# Binary_Sequencer_board2_controls.net
KiCad netlist of a schematic drawn in EAGLE
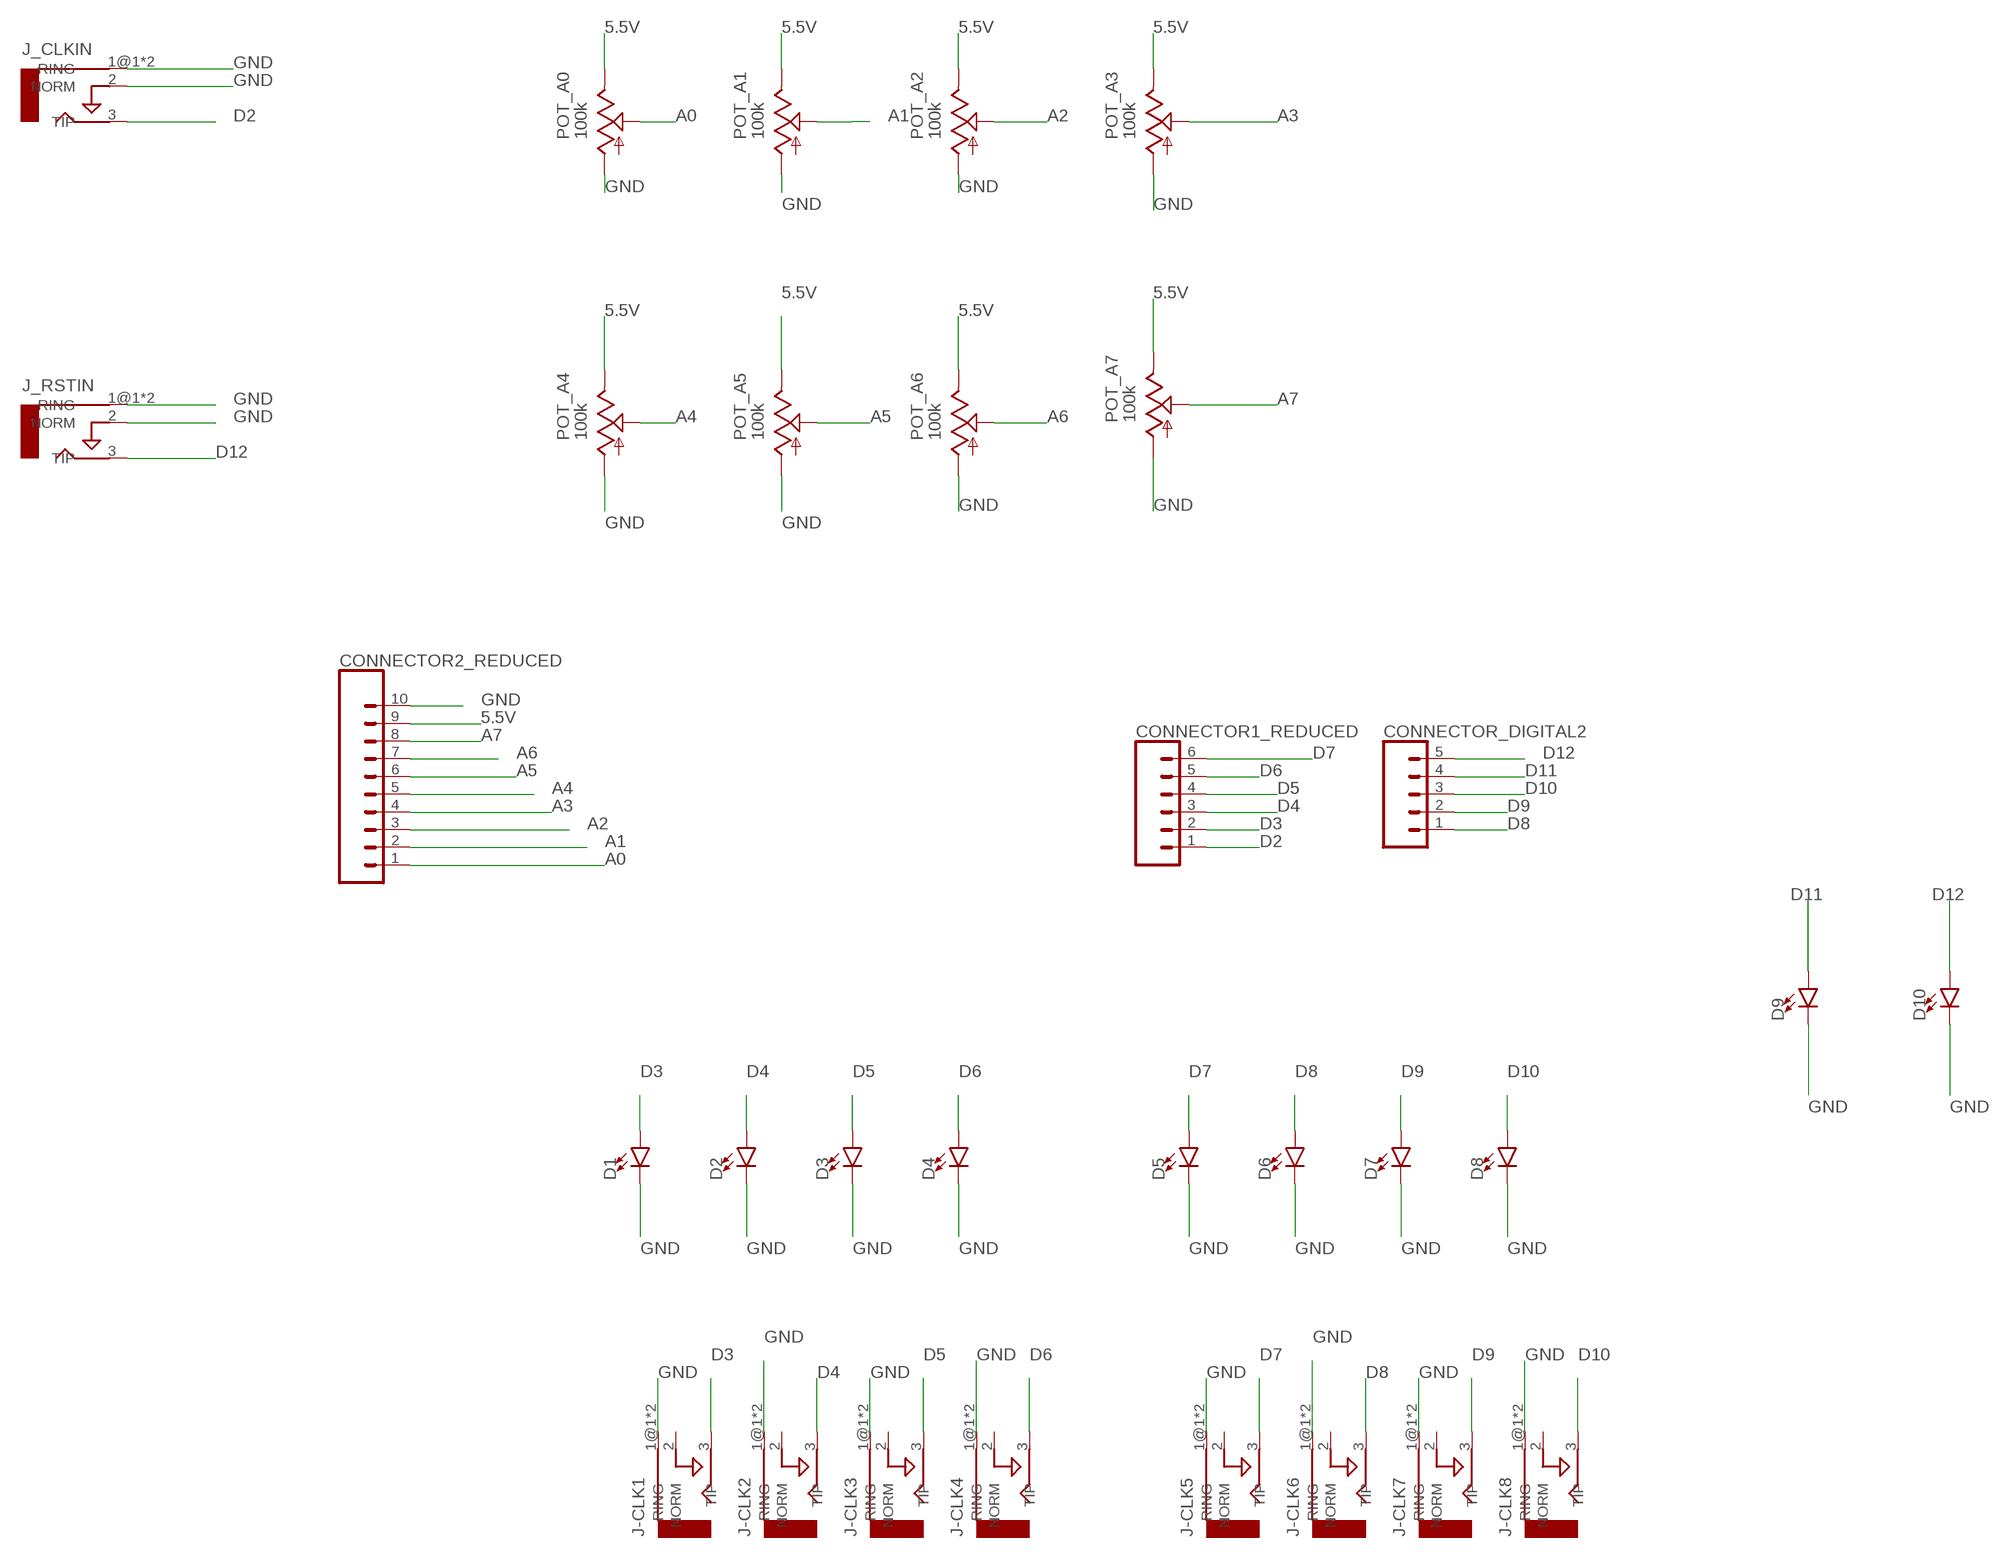
[diagram p0: schematic, sheet 1]

(export (version "E")
  (design (tool "Eeschema 10.0.6"))
  (components
    (comp (ref "CONNECTOR1_REDUCED")
      (value "CONN_06LONGPADS")
      (footprint "eagle-import:1X06_LONGPADS")
      (libsource (lib "eagle-import") (part "CONN_06LONGPADS"))
    )
    (comp (ref "CONNECTOR2_REDUCED")
      (value "CONN_10_LONGPADS10_LONGPADS")
      (footprint "eagle-import:1X10_LONGPADS")
      (libsource (lib "eagle-import") (part "CONN_10_LONGPADS10_LONGPADS"))
    )
    (comp (ref "CONNECTOR_DIGITAL2")
      (value "CONN_05PTH_LONGPADS")
      (footprint "eagle-import:1X05_LONGPADS")
      (libsource (lib "eagle-import") (part "CONN_05PTH_LONGPADS"))
    )
    (comp (ref "D1")
      (value "LED-3MM-NO_SILK")
      (footprint "eagle-import:LED_3MM-NS")
      (libsource (lib "eagle-import") (part "LED-3MM-NO_SILK"))
    )
    (comp (ref "D2")
      (value "LED-3MM-NO_SILK")
      (footprint "eagle-import:LED_3MM-NS")
      (libsource (lib "eagle-import") (part "LED-3MM-NO_SILK"))
    )
    (comp (ref "D3")
      (value "LED-3MM-NO_SILK")
      (footprint "eagle-import:LED_3MM-NS")
      (libsource (lib "eagle-import") (part "LED-3MM-NO_SILK"))
    )
    (comp (ref "D4")
      (value "LED-3MM-NO_SILK")
      (footprint "eagle-import:LED_3MM-NS")
      (libsource (lib "eagle-import") (part "LED-3MM-NO_SILK"))
    )
    (comp (ref "D5")
      (value "LED-3MM-NO_SILK")
      (footprint "eagle-import:LED_3MM-NS")
      (libsource (lib "eagle-import") (part "LED-3MM-NO_SILK"))
    )
    (comp (ref "D6")
      (value "LED-3MM-NO_SILK")
      (footprint "eagle-import:LED_3MM-NS")
      (libsource (lib "eagle-import") (part "LED-3MM-NO_SILK"))
    )
    (comp (ref "D7")
      (value "LED-3MM-NO_SILK")
      (footprint "eagle-import:LED_3MM-NS")
      (libsource (lib "eagle-import") (part "LED-3MM-NO_SILK"))
    )
    (comp (ref "D8")
      (value "LED-3MM-NO_SILK")
      (footprint "eagle-import:LED_3MM-NS")
      (libsource (lib "eagle-import") (part "LED-3MM-NO_SILK"))
    )
    (comp (ref "D9")
      (value "LED-3MM-NO_SILK")
      (footprint "eagle-import:LED_3MM-NS")
      (libsource (lib "eagle-import") (part "LED-3MM-NO_SILK"))
    )
    (comp (ref "D10")
      (value "LED-3MM-NO_SILK")
      (footprint "eagle-import:LED_3MM-NS")
      (libsource (lib "eagle-import") (part "LED-3MM-NO_SILK"))
    )
    (comp (ref "J-CLK1")
      (value "AUDIO-JACKERTHENVAR")
      (footprint "eagle-import:ERTHENVAR-JACK")
      (libsource (lib "eagle-import") (part "AUDIO-JACKERTHENVAR"))
    )
    (comp (ref "J-CLK2")
      (value "AUDIO-JACKERTHENVAR")
      (footprint "eagle-import:ERTHENVAR-JACK")
      (libsource (lib "eagle-import") (part "AUDIO-JACKERTHENVAR"))
    )
    (comp (ref "J-CLK3")
      (value "AUDIO-JACKERTHENVAR")
      (footprint "eagle-import:ERTHENVAR-JACK")
      (libsource (lib "eagle-import") (part "AUDIO-JACKERTHENVAR"))
    )
    (comp (ref "J-CLK4")
      (value "AUDIO-JACKERTHENVAR")
      (footprint "eagle-import:ERTHENVAR-JACK")
      (libsource (lib "eagle-import") (part "AUDIO-JACKERTHENVAR"))
    )
    (comp (ref "J-CLK5")
      (value "AUDIO-JACKERTHENVAR")
      (footprint "eagle-import:ERTHENVAR-JACK")
      (libsource (lib "eagle-import") (part "AUDIO-JACKERTHENVAR"))
    )
    (comp (ref "J-CLK6")
      (value "AUDIO-JACKERTHENVAR")
      (footprint "eagle-import:ERTHENVAR-JACK")
      (libsource (lib "eagle-import") (part "AUDIO-JACKERTHENVAR"))
    )
    (comp (ref "J-CLK7")
      (value "AUDIO-JACKERTHENVAR")
      (footprint "eagle-import:ERTHENVAR-JACK")
      (libsource (lib "eagle-import") (part "AUDIO-JACKERTHENVAR"))
    )
    (comp (ref "J-CLK8")
      (value "AUDIO-JACKERTHENVAR")
      (footprint "eagle-import:ERTHENVAR-JACK")
      (libsource (lib "eagle-import") (part "AUDIO-JACKERTHENVAR"))
    )
    (comp (ref "J_CLKIN")
      (value "AUDIO-JACKERTHENVAR")
      (footprint "eagle-import:ERTHENVAR-JACK")
      (libsource (lib "eagle-import") (part "AUDIO-JACKERTHENVAR"))
    )
    (comp (ref "J_RSTIN")
      (value "AUDIO-JACKERTHENVAR")
      (footprint "eagle-import:ERTHENVAR-JACK")
      (libsource (lib "eagle-import") (part "AUDIO-JACKERTHENVAR"))
    )
    (comp (ref "POT_A0")
      (value "100k")
      (footprint "eagle-import:9MM_SNAP-IN_POT")
      (libsource (lib "eagle-import") (part "9MM_SNAP-IN_POT_"))
    )
    (comp (ref "POT_A1")
      (value "100k")
      (footprint "eagle-import:9MM_SNAP-IN_POT")
      (libsource (lib "eagle-import") (part "9MM_SNAP-IN_POT_"))
    )
    (comp (ref "POT_A2")
      (value "100k")
      (footprint "eagle-import:9MM_SNAP-IN_POT")
      (libsource (lib "eagle-import") (part "9MM_SNAP-IN_POT_"))
    )
    (comp (ref "POT_A3")
      (value "100k")
      (footprint "eagle-import:9MM_SNAP-IN_POT")
      (libsource (lib "eagle-import") (part "9MM_SNAP-IN_POT_"))
    )
    (comp (ref "POT_A4")
      (value "100k")
      (footprint "eagle-import:9MM_SNAP-IN_POT")
      (libsource (lib "eagle-import") (part "9MM_SNAP-IN_POT_"))
    )
    (comp (ref "POT_A5")
      (value "100k")
      (footprint "eagle-import:9MM_SNAP-IN_POT")
      (libsource (lib "eagle-import") (part "9MM_SNAP-IN_POT_"))
    )
    (comp (ref "POT_A6")
      (value "100k")
      (footprint "eagle-import:9MM_SNAP-IN_POT")
      (libsource (lib "eagle-import") (part "9MM_SNAP-IN_POT_"))
    )
    (comp (ref "POT_A7")
      (value "100k")
      (footprint "eagle-import:9MM_SNAP-IN_POT")
      (libsource (lib "eagle-import") (part "9MM_SNAP-IN_POT_"))
    )
  )
  (nets
    (net (code "1") (name "/5.5V") (class "Default")
      (node (ref "CONNECTOR2_REDUCED") (pin "9") (pinfunction "9_9") (pintype "passive"))
      (node (ref "POT_A0") (pin "3") (pinfunction "E_3") (pintype "passive"))
      (node (ref "POT_A1") (pin "3") (pinfunction "E_3") (pintype "passive"))
      (node (ref "POT_A2") (pin "3") (pinfunction "E_3") (pintype "passive"))
      (node (ref "POT_A3") (pin "3") (pinfunction "E_3") (pintype "passive"))
      (node (ref "POT_A4") (pin "3") (pinfunction "E_3") (pintype "passive"))
      (node (ref "POT_A5") (pin "3") (pinfunction "E_3") (pintype "passive"))
      (node (ref "POT_A6") (pin "3") (pinfunction "E_3") (pintype "passive"))
      (node (ref "POT_A7") (pin "3") (pinfunction "E_3") (pintype "passive"))
    )
    (net (code "2") (name "/A0") (class "Default")
      (node (ref "CONNECTOR2_REDUCED") (pin "1") (pinfunction "1_1") (pintype "passive"))
      (node (ref "POT_A0") (pin "2") (pinfunction "S_2") (pintype "passive"))
    )
    (net (code "3") (name "/A1") (class "Default")
      (node (ref "CONNECTOR2_REDUCED") (pin "2") (pinfunction "2_2") (pintype "passive"))
      (node (ref "POT_A1") (pin "2") (pinfunction "S_2") (pintype "passive"))
    )
    (net (code "4") (name "/A2") (class "Default")
      (node (ref "CONNECTOR2_REDUCED") (pin "3") (pinfunction "3_3") (pintype "passive"))
      (node (ref "POT_A2") (pin "2") (pinfunction "S_2") (pintype "passive"))
    )
    (net (code "5") (name "/A3") (class "Default")
      (node (ref "CONNECTOR2_REDUCED") (pin "4") (pinfunction "4_4") (pintype "passive"))
      (node (ref "POT_A3") (pin "2") (pinfunction "S_2") (pintype "passive"))
    )
    (net (code "6") (name "/A4") (class "Default")
      (node (ref "CONNECTOR2_REDUCED") (pin "5") (pinfunction "5_5") (pintype "passive"))
      (node (ref "POT_A4") (pin "2") (pinfunction "S_2") (pintype "passive"))
    )
    (net (code "7") (name "/A5") (class "Default")
      (node (ref "CONNECTOR2_REDUCED") (pin "6") (pinfunction "6_6") (pintype "passive"))
      (node (ref "POT_A5") (pin "2") (pinfunction "S_2") (pintype "passive"))
    )
    (net (code "8") (name "/A6") (class "Default")
      (node (ref "CONNECTOR2_REDUCED") (pin "7") (pinfunction "7_7") (pintype "passive"))
      (node (ref "POT_A6") (pin "2") (pinfunction "S_2") (pintype "passive"))
    )
    (net (code "9") (name "/A7") (class "Default")
      (node (ref "CONNECTOR2_REDUCED") (pin "8") (pinfunction "8_8") (pintype "passive"))
      (node (ref "POT_A7") (pin "2") (pinfunction "S_2") (pintype "passive"))
    )
    (net (code "10") (name "/D2") (class "Default")
      (node (ref "CONNECTOR1_REDUCED") (pin "1") (pinfunction "1_1") (pintype "passive"))
      (node (ref "J_CLKIN") (pin "3") (pinfunction "TIP_3") (pintype "bidirectional"))
    )
    (net (code "11") (name "/D3") (class "Default")
      (node (ref "CONNECTOR1_REDUCED") (pin "2") (pinfunction "2_2") (pintype "passive"))
      (node (ref "D1") (pin "A") (pinfunction "A_A") (pintype "passive"))
      (node (ref "J-CLK1") (pin "3") (pinfunction "TIP_3") (pintype "bidirectional"))
    )
    (net (code "12") (name "/D4") (class "Default")
      (node (ref "CONNECTOR1_REDUCED") (pin "3") (pinfunction "3_3") (pintype "passive"))
      (node (ref "D2") (pin "A") (pinfunction "A_A") (pintype "passive"))
      (node (ref "J-CLK2") (pin "3") (pinfunction "TIP_3") (pintype "bidirectional"))
    )
    (net (code "13") (name "/D5") (class "Default")
      (node (ref "CONNECTOR1_REDUCED") (pin "4") (pinfunction "4_4") (pintype "passive"))
      (node (ref "D3") (pin "A") (pinfunction "A_A") (pintype "passive"))
      (node (ref "J-CLK3") (pin "3") (pinfunction "TIP_3") (pintype "bidirectional"))
    )
    (net (code "14") (name "/D6") (class "Default")
      (node (ref "CONNECTOR1_REDUCED") (pin "5") (pinfunction "5_5") (pintype "passive"))
      (node (ref "D4") (pin "A") (pinfunction "A_A") (pintype "passive"))
      (node (ref "J-CLK4") (pin "3") (pinfunction "TIP_3") (pintype "bidirectional"))
    )
    (net (code "15") (name "/D7") (class "Default")
      (node (ref "CONNECTOR1_REDUCED") (pin "6") (pinfunction "6_6") (pintype "passive"))
      (node (ref "D5") (pin "A") (pinfunction "A_A") (pintype "passive"))
      (node (ref "J-CLK5") (pin "3") (pinfunction "TIP_3") (pintype "bidirectional"))
    )
    (net (code "16") (name "/D8") (class "Default")
      (node (ref "CONNECTOR_DIGITAL2") (pin "1") (pinfunction "1_1") (pintype "passive"))
      (node (ref "D6") (pin "A") (pinfunction "A_A") (pintype "passive"))
      (node (ref "J-CLK6") (pin "3") (pinfunction "TIP_3") (pintype "bidirectional"))
    )
    (net (code "17") (name "/D9") (class "Default")
      (node (ref "CONNECTOR_DIGITAL2") (pin "2") (pinfunction "2_2") (pintype "passive"))
      (node (ref "D7") (pin "A") (pinfunction "A_A") (pintype "passive"))
      (node (ref "J-CLK7") (pin "3") (pinfunction "TIP_3") (pintype "bidirectional"))
    )
    (net (code "18") (name "/D10") (class "Default")
      (node (ref "CONNECTOR_DIGITAL2") (pin "3") (pinfunction "3_3") (pintype "passive"))
      (node (ref "D8") (pin "A") (pinfunction "A_A") (pintype "passive"))
      (node (ref "J-CLK8") (pin "3") (pinfunction "TIP_3") (pintype "bidirectional"))
    )
    (net (code "19") (name "/D11") (class "Default")
      (node (ref "CONNECTOR_DIGITAL2") (pin "4") (pinfunction "4_4") (pintype "passive"))
      (node (ref "D9") (pin "A") (pinfunction "A_A") (pintype "passive"))
    )
    (net (code "20") (name "/D12") (class "Default")
      (node (ref "CONNECTOR_DIGITAL2") (pin "5") (pinfunction "5_5") (pintype "passive"))
      (node (ref "D10") (pin "A") (pinfunction "A_A") (pintype "passive"))
      (node (ref "J_RSTIN") (pin "3") (pinfunction "TIP_3") (pintype "bidirectional"))
    )
    (net (code "21") (name "/GND") (class "Default")
      (node (ref "CONNECTOR2_REDUCED") (pin "10") (pinfunction "10_10") (pintype "passive"))
      (node (ref "D1") (pin "K") (pinfunction "C_K") (pintype "passive"))
      (node (ref "D10") (pin "K") (pinfunction "C_K") (pintype "passive"))
      (node (ref "D2") (pin "K") (pinfunction "C_K") (pintype "passive"))
      (node (ref "D3") (pin "K") (pinfunction "C_K") (pintype "passive"))
      (node (ref "D4") (pin "K") (pinfunction "C_K") (pintype "passive"))
      (node (ref "D5") (pin "K") (pinfunction "C_K") (pintype "passive"))
      (node (ref "D6") (pin "K") (pinfunction "C_K") (pintype "passive"))
      (node (ref "D7") (pin "K") (pinfunction "C_K") (pintype "passive"))
      (node (ref "D8") (pin "K") (pinfunction "C_K") (pintype "passive"))
      (node (ref "D9") (pin "K") (pinfunction "C_K") (pintype "passive"))
      (node (ref "J-CLK1") (pin "1@1") (pinfunction "RING_1@1") (pintype "bidirectional"))
      (node (ref "J-CLK1") (pin "1@2") (pinfunction "RING_1@2") (pintype "bidirectional"))
      (node (ref "J-CLK2") (pin "1@1") (pinfunction "RING_1@1") (pintype "bidirectional"))
      (node (ref "J-CLK2") (pin "1@2") (pinfunction "RING_1@2") (pintype "bidirectional"))
      (node (ref "J-CLK3") (pin "1@1") (pinfunction "RING_1@1") (pintype "bidirectional"))
      (node (ref "J-CLK3") (pin "1@2") (pinfunction "RING_1@2") (pintype "bidirectional"))
      (node (ref "J-CLK4") (pin "1@1") (pinfunction "RING_1@1") (pintype "bidirectional"))
      (node (ref "J-CLK4") (pin "1@2") (pinfunction "RING_1@2") (pintype "bidirectional"))
      (node (ref "J-CLK5") (pin "1@1") (pinfunction "RING_1@1") (pintype "bidirectional"))
      (node (ref "J-CLK5") (pin "1@2") (pinfunction "RING_1@2") (pintype "bidirectional"))
      (node (ref "J-CLK6") (pin "1@1") (pinfunction "RING_1@1") (pintype "bidirectional"))
      (node (ref "J-CLK6") (pin "1@2") (pinfunction "RING_1@2") (pintype "bidirectional"))
      (node (ref "J-CLK7") (pin "1@1") (pinfunction "RING_1@1") (pintype "bidirectional"))
      (node (ref "J-CLK7") (pin "1@2") (pinfunction "RING_1@2") (pintype "bidirectional"))
      (node (ref "J-CLK8") (pin "1@1") (pinfunction "RING_1@1") (pintype "bidirectional"))
      (node (ref "J-CLK8") (pin "1@2") (pinfunction "RING_1@2") (pintype "bidirectional"))
      (node (ref "J_CLKIN") (pin "1@1") (pinfunction "RING_1@1") (pintype "bidirectional"))
      (node (ref "J_CLKIN") (pin "1@2") (pinfunction "RING_1@2") (pintype "bidirectional"))
      (node (ref "J_CLKIN") (pin "2") (pinfunction "NORM_2") (pintype "bidirectional"))
      (node (ref "J_RSTIN") (pin "1@1") (pinfunction "RING_1@1") (pintype "bidirectional"))
      (node (ref "J_RSTIN") (pin "1@2") (pinfunction "RING_1@2") (pintype "bidirectional"))
      (node (ref "J_RSTIN") (pin "2") (pinfunction "NORM_2") (pintype "bidirectional"))
      (node (ref "POT_A0") (pin "1") (pinfunction "A_1") (pintype "passive"))
      (node (ref "POT_A1") (pin "1") (pinfunction "A_1") (pintype "passive"))
      (node (ref "POT_A2") (pin "1") (pinfunction "A_1") (pintype "passive"))
      (node (ref "POT_A3") (pin "1") (pinfunction "A_1") (pintype "passive"))
      (node (ref "POT_A4") (pin "1") (pinfunction "A_1") (pintype "passive"))
      (node (ref "POT_A5") (pin "1") (pinfunction "A_1") (pintype "passive"))
      (node (ref "POT_A6") (pin "1") (pinfunction "A_1") (pintype "passive"))
      (node (ref "POT_A7") (pin "1") (pinfunction "A_1") (pintype "passive"))
    )
    (net (code "22") (name "unconnected-(J-CLK1-NORM-Pad2)") (class "Default")
      (node (ref "J-CLK1") (pin "2") (pinfunction "NORM_2") (pintype "bidirectional"))
    )
    (net (code "23") (name "unconnected-(J-CLK2-NORM-Pad2)") (class "Default")
      (node (ref "J-CLK2") (pin "2") (pinfunction "NORM_2") (pintype "bidirectional"))
    )
    (net (code "24") (name "unconnected-(J-CLK3-NORM-Pad2)") (class "Default")
      (node (ref "J-CLK3") (pin "2") (pinfunction "NORM_2") (pintype "bidirectional"))
    )
    (net (code "25") (name "unconnected-(J-CLK4-NORM-Pad2)") (class "Default")
      (node (ref "J-CLK4") (pin "2") (pinfunction "NORM_2") (pintype "bidirectional"))
    )
    (net (code "26") (name "unconnected-(J-CLK5-NORM-Pad2)") (class "Default")
      (node (ref "J-CLK5") (pin "2") (pinfunction "NORM_2") (pintype "bidirectional"))
    )
    (net (code "27") (name "unconnected-(J-CLK6-NORM-Pad2)") (class "Default")
      (node (ref "J-CLK6") (pin "2") (pinfunction "NORM_2") (pintype "bidirectional"))
    )
    (net (code "28") (name "unconnected-(J-CLK7-NORM-Pad2)") (class "Default")
      (node (ref "J-CLK7") (pin "2") (pinfunction "NORM_2") (pintype "bidirectional"))
    )
    (net (code "29") (name "unconnected-(J-CLK8-NORM-Pad2)") (class "Default")
      (node (ref "J-CLK8") (pin "2") (pinfunction "NORM_2") (pintype "bidirectional"))
    )
  )
)
